# LB_BIT_i6_DIMMER-v02_rev1.net
KiCad netlist of a schematic drawn in EAGLE
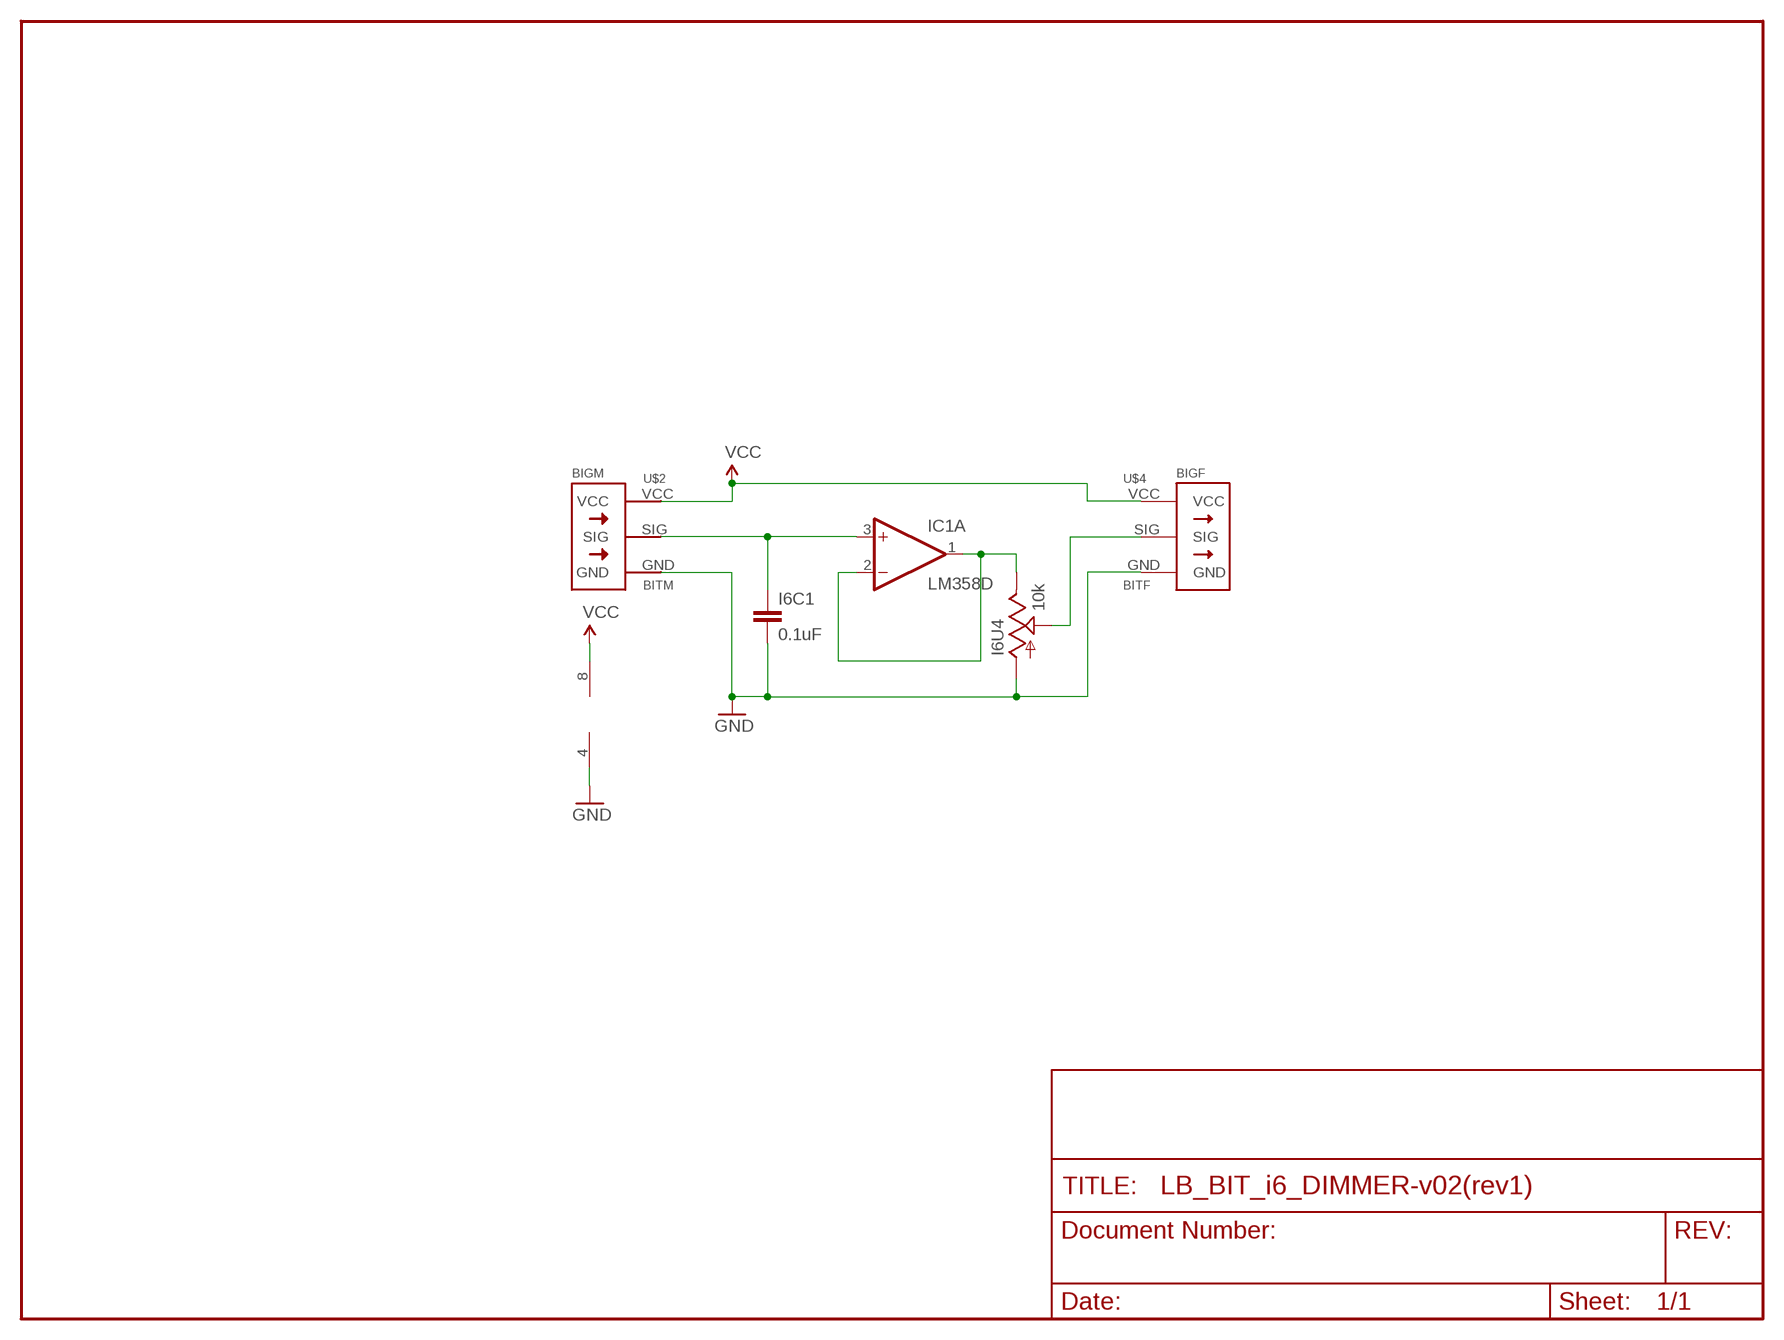
[diagram p0: schematic, sheet 1]

(export (version "E")
  (design (tool "Eeschema 10.0.6"))
  (components
    (comp (ref "I6C1")
      (value "0.1uF")
      (footprint "eagle-import:1206")
      (libsource (lib "eagle-import") (part "CAP1206"))
    )
    (comp (ref "I6U4")
      (value "10k")
      (footprint "eagle-import:POT_ALPHA_RV16AF-20")
      (libsource (lib "eagle-import") (part "POT-RV16AF-20"))
    )
    (comp (ref "IC1")
      (value "LM358D")
      (footprint "eagle-import:SO08")
      (libsource (lib "eagle-import") (part "LM358D"))
    )
    (comp (ref "U$2")
      (value "BITM")
      (footprint "eagle-import:BITM")
      (libsource (lib "eagle-import") (part "BITM"))
    )
    (comp (ref "U$4")
      (value "BITF")
      (footprint "eagle-import:BITM")
      (libsource (lib "eagle-import") (part "BITF"))
    )
  )
  (nets
    (net (code "1") (name "GND") (class "Default")
      (node (ref "I6C1") (pin "2") (pinfunction "2_2") (pintype "passive"))
      (node (ref "I6U4") (pin "1") (pinfunction "A_1") (pintype "passive"))
      (node (ref "IC1") (pin "4") (pinfunction "V-_4") (pintype "power_in"))
      (node (ref "U$2") (pin "GND") (pinfunction "GND_GND") (pintype "bidirectional"))
      (node (ref "U$4") (pin "GND") (pinfunction "GND_GND") (pintype "bidirectional"))
    )
    (net (code "2") (name "Net-(I6U4-E)") (class "Default")
      (node (ref "I6U4") (pin "3") (pinfunction "E_3") (pintype "passive"))
      (node (ref "IC1") (pin "1") (pinfunction "OUT_1") (pintype "output"))
      (node (ref "IC1") (pin "2") (pinfunction "-IN_2") (pintype "input"))
    )
    (net (code "3") (name "Net-(I6U4-S)") (class "Default")
      (node (ref "I6U4") (pin "2") (pinfunction "S_2") (pintype "passive"))
      (node (ref "U$4") (pin "SIG") (pinfunction "SIG_SIG") (pintype "bidirectional"))
    )
    (net (code "4") (name "Net-(IC1A-+IN)") (class "Default")
      (node (ref "I6C1") (pin "1") (pinfunction "1_1") (pintype "passive"))
      (node (ref "IC1") (pin "3") (pinfunction "+IN_3") (pintype "input"))
      (node (ref "U$2") (pin "SIG") (pinfunction "SIG_SIG") (pintype "bidirectional"))
    )
    (net (code "5") (name "VCC") (class "Default")
      (node (ref "IC1") (pin "8") (pinfunction "V+_8") (pintype "power_in"))
      (node (ref "U$2") (pin "VCC") (pinfunction "VCC_VCC") (pintype "bidirectional"))
      (node (ref "U$4") (pin "VCC") (pinfunction "VCC_VCC") (pintype "bidirectional"))
    )
  )
)
